# LED_segment.net
KiCad netlist of a schematic drawn in EAGLE
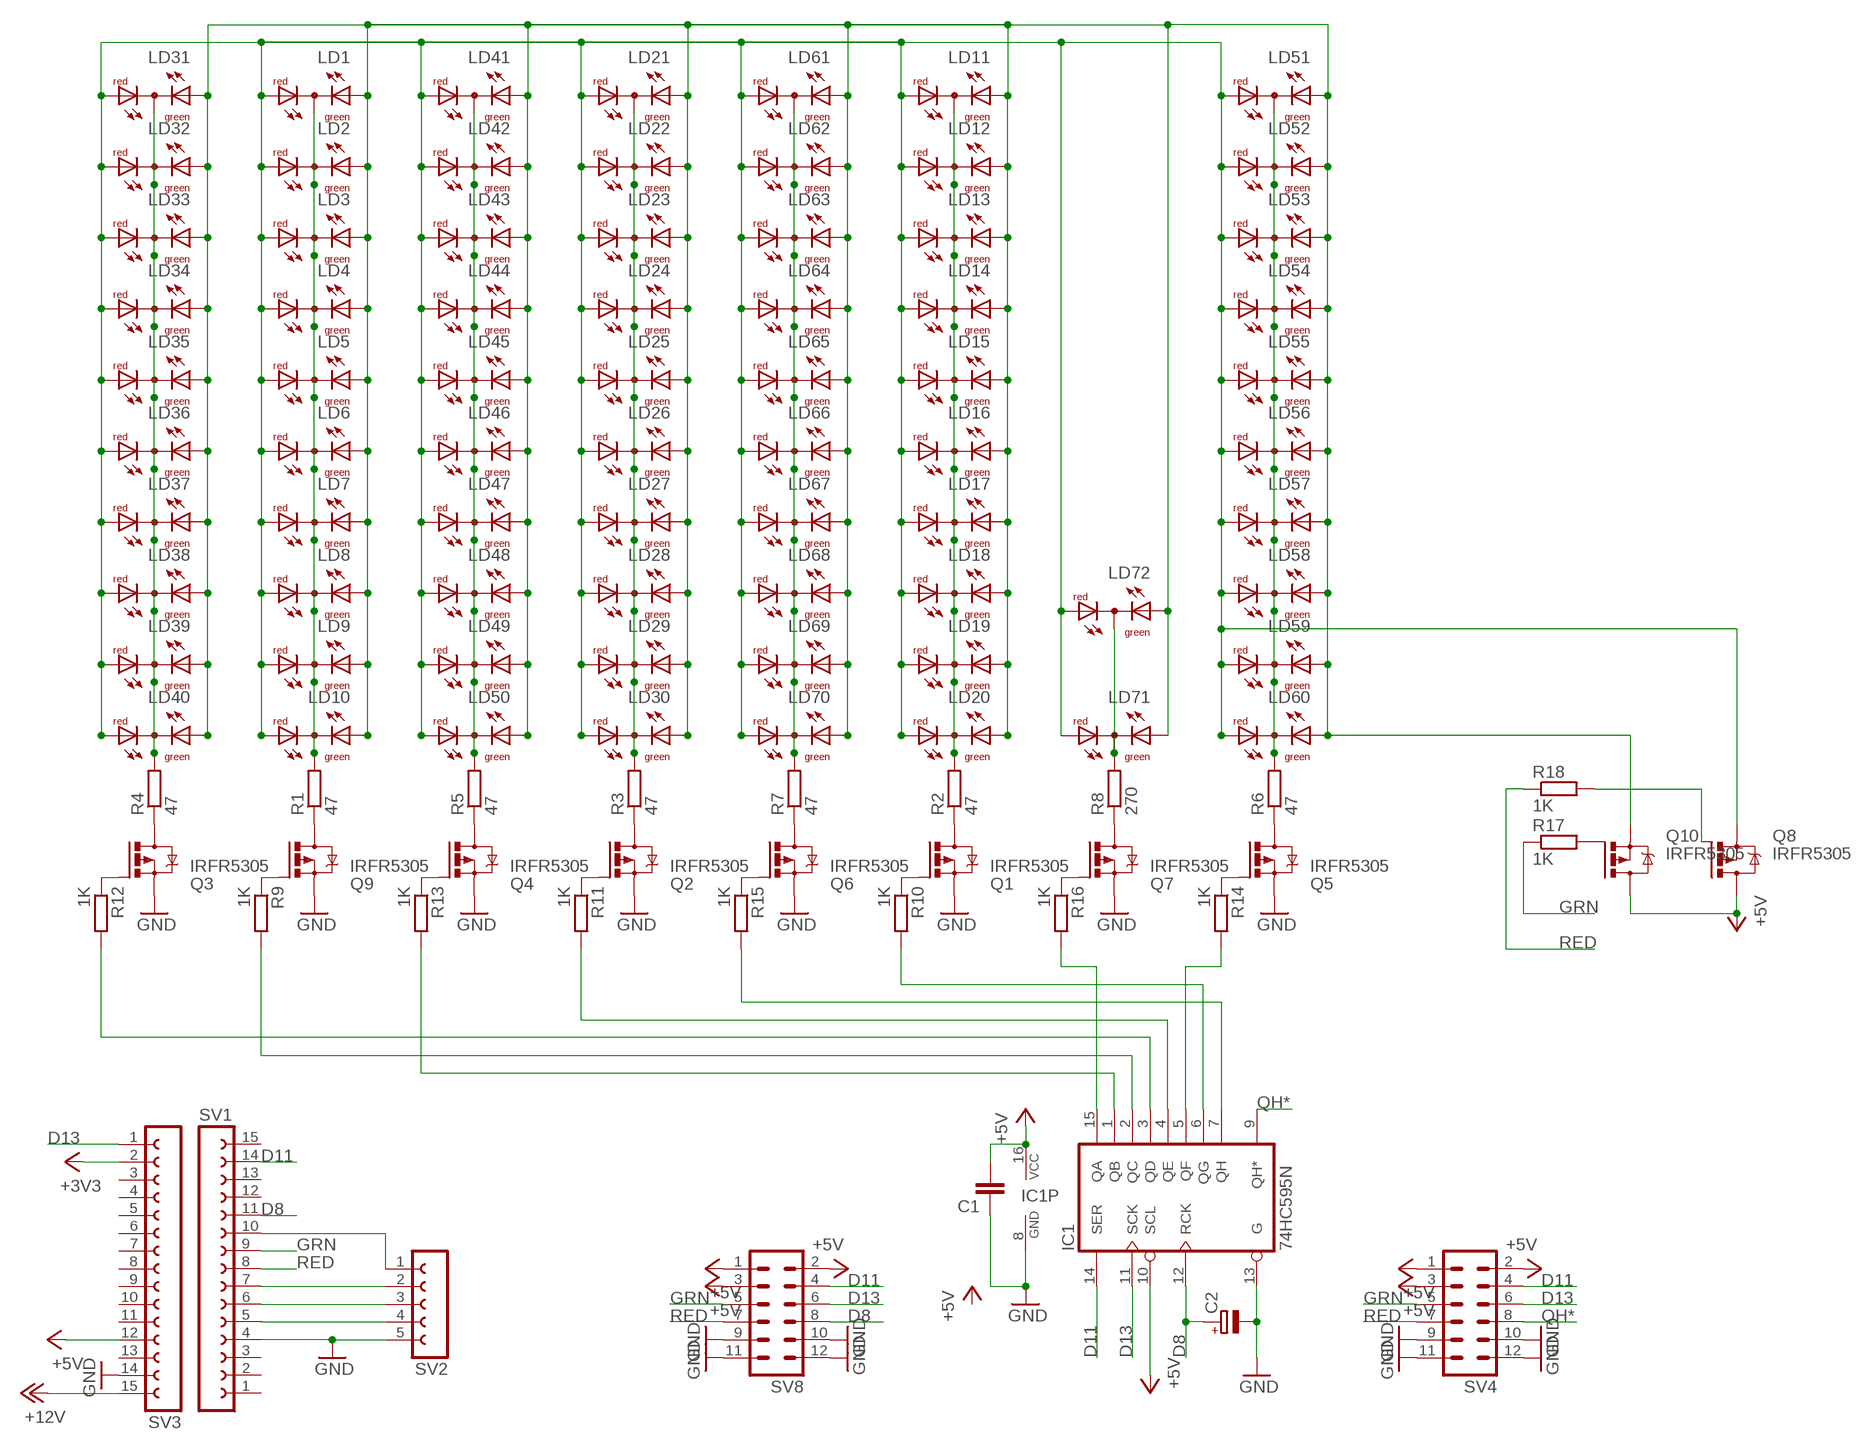
[diagram p0: schematic, sheet 1]

(export (version "E")
  (design (tool "Eeschema 10.0.6"))
  (components
    (comp (ref "C1")
      (value "C-EU050-030X075")
      (footprint "eagle-import:C050-030X075")
      (libsource (lib "eagle-import") (part "C-EU050-030X075"))
    )
    (comp (ref "C2")
      (value "CPOL-EUE2.5-7")
      (footprint "eagle-import:E2,5-7")
      (libsource (lib "eagle-import") (part "CPOL-EUE2.5-7"))
    )
    (comp (ref "IC1")
      (value "74HC595N")
      (footprint "eagle-import:DIL16")
      (libsource (lib "eagle-import") (part "74595NHC"))
    )
    (comp (ref "LD1")
      (value "DUOLED-RG-C")
      (footprint "eagle-import:DUOLED-C-5MM")
      (libsource (lib "eagle-import") (part "DUOLED-RG-C"))
    )
    (comp (ref "LD2")
      (value "DUOLED-RG-C")
      (footprint "eagle-import:DUOLED-C-5MM")
      (libsource (lib "eagle-import") (part "DUOLED-RG-C"))
    )
    (comp (ref "LD3")
      (value "DUOLED-RG-C")
      (footprint "eagle-import:DUOLED-C-5MM")
      (libsource (lib "eagle-import") (part "DUOLED-RG-C"))
    )
    (comp (ref "LD4")
      (value "DUOLED-RG-C")
      (footprint "eagle-import:DUOLED-C-5MM")
      (libsource (lib "eagle-import") (part "DUOLED-RG-C"))
    )
    (comp (ref "LD5")
      (value "DUOLED-RG-C")
      (footprint "eagle-import:DUOLED-C-5MM")
      (libsource (lib "eagle-import") (part "DUOLED-RG-C"))
    )
    (comp (ref "LD6")
      (value "DUOLED-RG-C")
      (footprint "eagle-import:DUOLED-C-5MM")
      (libsource (lib "eagle-import") (part "DUOLED-RG-C"))
    )
    (comp (ref "LD7")
      (value "DUOLED-RG-C")
      (footprint "eagle-import:DUOLED-C-5MM")
      (libsource (lib "eagle-import") (part "DUOLED-RG-C"))
    )
    (comp (ref "LD8")
      (value "DUOLED-RG-C")
      (footprint "eagle-import:DUOLED-C-5MM")
      (libsource (lib "eagle-import") (part "DUOLED-RG-C"))
    )
    (comp (ref "LD9")
      (value "DUOLED-RG-C")
      (footprint "eagle-import:DUOLED-C-5MM")
      (libsource (lib "eagle-import") (part "DUOLED-RG-C"))
    )
    (comp (ref "LD10")
      (value "DUOLED-RG-C")
      (footprint "eagle-import:DUOLED-C-5MM")
      (libsource (lib "eagle-import") (part "DUOLED-RG-C"))
    )
    (comp (ref "LD11")
      (value "DUOLED-RG-C")
      (footprint "eagle-import:DUOLED-C-5MM")
      (libsource (lib "eagle-import") (part "DUOLED-RG-C"))
    )
    (comp (ref "LD12")
      (value "DUOLED-RG-C")
      (footprint "eagle-import:DUOLED-C-5MM")
      (libsource (lib "eagle-import") (part "DUOLED-RG-C"))
    )
    (comp (ref "LD13")
      (value "DUOLED-RG-C")
      (footprint "eagle-import:DUOLED-C-5MM")
      (libsource (lib "eagle-import") (part "DUOLED-RG-C"))
    )
    (comp (ref "LD14")
      (value "DUOLED-RG-C")
      (footprint "eagle-import:DUOLED-C-5MM")
      (libsource (lib "eagle-import") (part "DUOLED-RG-C"))
    )
    (comp (ref "LD15")
      (value "DUOLED-RG-C")
      (footprint "eagle-import:DUOLED-C-5MM")
      (libsource (lib "eagle-import") (part "DUOLED-RG-C"))
    )
    (comp (ref "LD16")
      (value "DUOLED-RG-C")
      (footprint "eagle-import:DUOLED-C-5MM")
      (libsource (lib "eagle-import") (part "DUOLED-RG-C"))
    )
    (comp (ref "LD17")
      (value "DUOLED-RG-C")
      (footprint "eagle-import:DUOLED-C-5MM")
      (libsource (lib "eagle-import") (part "DUOLED-RG-C"))
    )
    (comp (ref "LD18")
      (value "DUOLED-RG-C")
      (footprint "eagle-import:DUOLED-C-5MM")
      (libsource (lib "eagle-import") (part "DUOLED-RG-C"))
    )
    (comp (ref "LD19")
      (value "DUOLED-RG-C")
      (footprint "eagle-import:DUOLED-C-5MM")
      (libsource (lib "eagle-import") (part "DUOLED-RG-C"))
    )
    (comp (ref "LD20")
      (value "DUOLED-RG-C")
      (footprint "eagle-import:DUOLED-C-5MM")
      (libsource (lib "eagle-import") (part "DUOLED-RG-C"))
    )
    (comp (ref "LD21")
      (value "DUOLED-RG-C")
      (footprint "eagle-import:DUOLED-C-5MM")
      (libsource (lib "eagle-import") (part "DUOLED-RG-C"))
    )
    (comp (ref "LD22")
      (value "DUOLED-RG-C")
      (footprint "eagle-import:DUOLED-C-5MM")
      (libsource (lib "eagle-import") (part "DUOLED-RG-C"))
    )
    (comp (ref "LD23")
      (value "DUOLED-RG-C")
      (footprint "eagle-import:DUOLED-C-5MM")
      (libsource (lib "eagle-import") (part "DUOLED-RG-C"))
    )
    (comp (ref "LD24")
      (value "DUOLED-RG-C")
      (footprint "eagle-import:DUOLED-C-5MM")
      (libsource (lib "eagle-import") (part "DUOLED-RG-C"))
    )
    (comp (ref "LD25")
      (value "DUOLED-RG-C")
      (footprint "eagle-import:DUOLED-C-5MM")
      (libsource (lib "eagle-import") (part "DUOLED-RG-C"))
    )
    (comp (ref "LD26")
      (value "DUOLED-RG-C")
      (footprint "eagle-import:DUOLED-C-5MM")
      (libsource (lib "eagle-import") (part "DUOLED-RG-C"))
    )
    (comp (ref "LD27")
      (value "DUOLED-RG-C")
      (footprint "eagle-import:DUOLED-C-5MM")
      (libsource (lib "eagle-import") (part "DUOLED-RG-C"))
    )
    (comp (ref "LD28")
      (value "DUOLED-RG-C")
      (footprint "eagle-import:DUOLED-C-5MM")
      (libsource (lib "eagle-import") (part "DUOLED-RG-C"))
    )
    (comp (ref "LD29")
      (value "DUOLED-RG-C")
      (footprint "eagle-import:DUOLED-C-5MM")
      (libsource (lib "eagle-import") (part "DUOLED-RG-C"))
    )
    (comp (ref "LD30")
      (value "DUOLED-RG-C")
      (footprint "eagle-import:DUOLED-C-5MM")
      (libsource (lib "eagle-import") (part "DUOLED-RG-C"))
    )
    (comp (ref "LD31")
      (value "DUOLED-RG-C")
      (footprint "eagle-import:DUOLED-C-5MM")
      (libsource (lib "eagle-import") (part "DUOLED-RG-C"))
    )
    (comp (ref "LD32")
      (value "DUOLED-RG-C")
      (footprint "eagle-import:DUOLED-C-5MM")
      (libsource (lib "eagle-import") (part "DUOLED-RG-C"))
    )
    (comp (ref "LD33")
      (value "DUOLED-RG-C")
      (footprint "eagle-import:DUOLED-C-5MM")
      (libsource (lib "eagle-import") (part "DUOLED-RG-C"))
    )
    (comp (ref "LD34")
      (value "DUOLED-RG-C")
      (footprint "eagle-import:DUOLED-C-5MM")
      (libsource (lib "eagle-import") (part "DUOLED-RG-C"))
    )
    (comp (ref "LD35")
      (value "DUOLED-RG-C")
      (footprint "eagle-import:DUOLED-C-5MM")
      (libsource (lib "eagle-import") (part "DUOLED-RG-C"))
    )
    (comp (ref "LD36")
      (value "DUOLED-RG-C")
      (footprint "eagle-import:DUOLED-C-5MM")
      (libsource (lib "eagle-import") (part "DUOLED-RG-C"))
    )
    (comp (ref "LD37")
      (value "DUOLED-RG-C")
      (footprint "eagle-import:DUOLED-C-5MM")
      (libsource (lib "eagle-import") (part "DUOLED-RG-C"))
    )
    (comp (ref "LD38")
      (value "DUOLED-RG-C")
      (footprint "eagle-import:DUOLED-C-5MM")
      (libsource (lib "eagle-import") (part "DUOLED-RG-C"))
    )
    (comp (ref "LD39")
      (value "DUOLED-RG-C")
      (footprint "eagle-import:DUOLED-C-5MM")
      (libsource (lib "eagle-import") (part "DUOLED-RG-C"))
    )
    (comp (ref "LD40")
      (value "DUOLED-RG-C")
      (footprint "eagle-import:DUOLED-C-5MM")
      (libsource (lib "eagle-import") (part "DUOLED-RG-C"))
    )
    (comp (ref "LD41")
      (value "DUOLED-RG-C")
      (footprint "eagle-import:DUOLED-C-5MM")
      (libsource (lib "eagle-import") (part "DUOLED-RG-C"))
    )
    (comp (ref "LD42")
      (value "DUOLED-RG-C")
      (footprint "eagle-import:DUOLED-C-5MM")
      (libsource (lib "eagle-import") (part "DUOLED-RG-C"))
    )
    (comp (ref "LD43")
      (value "DUOLED-RG-C")
      (footprint "eagle-import:DUOLED-C-5MM")
      (libsource (lib "eagle-import") (part "DUOLED-RG-C"))
    )
    (comp (ref "LD44")
      (value "DUOLED-RG-C")
      (footprint "eagle-import:DUOLED-C-5MM")
      (libsource (lib "eagle-import") (part "DUOLED-RG-C"))
    )
    (comp (ref "LD45")
      (value "DUOLED-RG-C")
      (footprint "eagle-import:DUOLED-C-5MM")
      (libsource (lib "eagle-import") (part "DUOLED-RG-C"))
    )
    (comp (ref "LD46")
      (value "DUOLED-RG-C")
      (footprint "eagle-import:DUOLED-C-5MM")
      (libsource (lib "eagle-import") (part "DUOLED-RG-C"))
    )
    (comp (ref "LD47")
      (value "DUOLED-RG-C")
      (footprint "eagle-import:DUOLED-C-5MM")
      (libsource (lib "eagle-import") (part "DUOLED-RG-C"))
    )
    (comp (ref "LD48")
      (value "DUOLED-RG-C")
      (footprint "eagle-import:DUOLED-C-5MM")
      (libsource (lib "eagle-import") (part "DUOLED-RG-C"))
    )
    (comp (ref "LD49")
      (value "DUOLED-RG-C")
      (footprint "eagle-import:DUOLED-C-5MM")
      (libsource (lib "eagle-import") (part "DUOLED-RG-C"))
    )
    (comp (ref "LD50")
      (value "DUOLED-RG-C")
      (footprint "eagle-import:DUOLED-C-5MM")
      (libsource (lib "eagle-import") (part "DUOLED-RG-C"))
    )
    (comp (ref "LD51")
      (value "DUOLED-RG-C")
      (footprint "eagle-import:DUOLED-C-5MM")
      (libsource (lib "eagle-import") (part "DUOLED-RG-C"))
    )
    (comp (ref "LD52")
      (value "DUOLED-RG-C")
      (footprint "eagle-import:DUOLED-C-5MM")
      (libsource (lib "eagle-import") (part "DUOLED-RG-C"))
    )
    (comp (ref "LD53")
      (value "DUOLED-RG-C")
      (footprint "eagle-import:DUOLED-C-5MM")
      (libsource (lib "eagle-import") (part "DUOLED-RG-C"))
    )
    (comp (ref "LD54")
      (value "DUOLED-RG-C")
      (footprint "eagle-import:DUOLED-C-5MM")
      (libsource (lib "eagle-import") (part "DUOLED-RG-C"))
    )
    (comp (ref "LD55")
      (value "DUOLED-RG-C")
      (footprint "eagle-import:DUOLED-C-5MM")
      (libsource (lib "eagle-import") (part "DUOLED-RG-C"))
    )
    (comp (ref "LD56")
      (value "DUOLED-RG-C")
      (footprint "eagle-import:DUOLED-C-5MM")
      (libsource (lib "eagle-import") (part "DUOLED-RG-C"))
    )
    (comp (ref "LD57")
      (value "DUOLED-RG-C")
      (footprint "eagle-import:DUOLED-C-5MM")
      (libsource (lib "eagle-import") (part "DUOLED-RG-C"))
    )
    (comp (ref "LD58")
      (value "DUOLED-RG-C")
      (footprint "eagle-import:DUOLED-C-5MM")
      (libsource (lib "eagle-import") (part "DUOLED-RG-C"))
    )
    (comp (ref "LD59")
      (value "DUOLED-RG-C")
      (footprint "eagle-import:DUOLED-C-5MM")
      (libsource (lib "eagle-import") (part "DUOLED-RG-C"))
    )
    (comp (ref "LD60")
      (value "DUOLED-RG-C")
      (footprint "eagle-import:DUOLED-C-5MM")
      (libsource (lib "eagle-import") (part "DUOLED-RG-C"))
    )
    (comp (ref "LD61")
      (value "DUOLED-RG-C")
      (footprint "eagle-import:DUOLED-C-5MM")
      (libsource (lib "eagle-import") (part "DUOLED-RG-C"))
    )
    (comp (ref "LD62")
      (value "DUOLED-RG-C")
      (footprint "eagle-import:DUOLED-C-5MM")
      (libsource (lib "eagle-import") (part "DUOLED-RG-C"))
    )
    (comp (ref "LD63")
      (value "DUOLED-RG-C")
      (footprint "eagle-import:DUOLED-C-5MM")
      (libsource (lib "eagle-import") (part "DUOLED-RG-C"))
    )
    (comp (ref "LD64")
      (value "DUOLED-RG-C")
      (footprint "eagle-import:DUOLED-C-5MM")
      (libsource (lib "eagle-import") (part "DUOLED-RG-C"))
    )
    (comp (ref "LD65")
      (value "DUOLED-RG-C")
      (footprint "eagle-import:DUOLED-C-5MM")
      (libsource (lib "eagle-import") (part "DUOLED-RG-C"))
    )
    (comp (ref "LD66")
      (value "DUOLED-RG-C")
      (footprint "eagle-import:DUOLED-C-5MM")
      (libsource (lib "eagle-import") (part "DUOLED-RG-C"))
    )
    (comp (ref "LD67")
      (value "DUOLED-RG-C")
      (footprint "eagle-import:DUOLED-C-5MM")
      (libsource (lib "eagle-import") (part "DUOLED-RG-C"))
    )
    (comp (ref "LD68")
      (value "DUOLED-RG-C")
      (footprint "eagle-import:DUOLED-C-5MM")
      (libsource (lib "eagle-import") (part "DUOLED-RG-C"))
    )
    (comp (ref "LD69")
      (value "DUOLED-RG-C")
      (footprint "eagle-import:DUOLED-C-5MM")
      (libsource (lib "eagle-import") (part "DUOLED-RG-C"))
    )
    (comp (ref "LD70")
      (value "DUOLED-RG-C")
      (footprint "eagle-import:DUOLED-C-5MM")
      (libsource (lib "eagle-import") (part "DUOLED-RG-C"))
    )
    (comp (ref "LD71")
      (value "DUOLED-RG-C")
      (footprint "eagle-import:DUOLED-C-5MM")
      (libsource (lib "eagle-import") (part "DUOLED-RG-C"))
    )
    (comp (ref "LD72")
      (value "DUOLED-RG-C")
      (footprint "eagle-import:DUOLED-C-5MM")
      (libsource (lib "eagle-import") (part "DUOLED-RG-C"))
    )
    (comp (ref "Q1")
      (value "IRFR5305")
      (footprint "eagle-import:D-PAK_TO252AA")
      (libsource (lib "eagle-import") (part "IRF?5305R"))
    )
    (comp (ref "Q2")
      (value "IRFR5305")
      (footprint "eagle-import:D-PAK_TO252AA")
      (libsource (lib "eagle-import") (part "IRF?5305R"))
    )
    (comp (ref "Q3")
      (value "IRFR5305")
      (footprint "eagle-import:D-PAK_TO252AA")
      (libsource (lib "eagle-import") (part "IRF?5305R"))
    )
    (comp (ref "Q4")
      (value "IRFR5305")
      (footprint "eagle-import:D-PAK_TO252AA")
      (libsource (lib "eagle-import") (part "IRF?5305R"))
    )
    (comp (ref "Q5")
      (value "IRFR5305")
      (footprint "eagle-import:D-PAK_TO252AA")
      (libsource (lib "eagle-import") (part "IRF?5305R"))
    )
    (comp (ref "Q6")
      (value "IRFR5305")
      (footprint "eagle-import:D-PAK_TO252AA")
      (libsource (lib "eagle-import") (part "IRF?5305R"))
    )
    (comp (ref "Q7")
      (value "IRFR5305")
      (footprint "eagle-import:D-PAK_TO252AA")
      (libsource (lib "eagle-import") (part "IRF?5305R"))
    )
    (comp (ref "Q8")
      (value "IRFR5305")
      (footprint "eagle-import:D-PAK_TO252AA")
      (libsource (lib "eagle-import") (part "IRF?5305R"))
    )
    (comp (ref "Q9")
      (value "IRFR5305")
      (footprint "eagle-import:D-PAK_TO252AA")
      (libsource (lib "eagle-import") (part "IRF?5305R"))
    )
    (comp (ref "Q10")
      (value "IRFR5305")
      (footprint "eagle-import:D-PAK_TO252AA")
      (libsource (lib "eagle-import") (part "IRF?5305R"))
    )
    (comp (ref "R1")
      (value "47")
      (footprint "eagle-import:0204_7")
      (libsource (lib "eagle-import") (part "R-EU_0204/7"))
    )
    (comp (ref "R2")
      (value "47")
      (footprint "eagle-import:0204_7")
      (libsource (lib "eagle-import") (part "R-EU_0204/7"))
    )
    (comp (ref "R3")
      (value "47")
      (footprint "eagle-import:0204_7")
      (libsource (lib "eagle-import") (part "R-EU_0204/7"))
    )
    (comp (ref "R4")
      (value "47")
      (footprint "eagle-import:0204_7")
      (libsource (lib "eagle-import") (part "R-EU_0204/7"))
    )
    (comp (ref "R5")
      (value "47")
      (footprint "eagle-import:0204_7")
      (libsource (lib "eagle-import") (part "R-EU_0204/7"))
    )
    (comp (ref "R6")
      (value "47")
      (footprint "eagle-import:0204_7")
      (libsource (lib "eagle-import") (part "R-EU_0204/7"))
    )
    (comp (ref "R7")
      (value "47")
      (footprint "eagle-import:0207_5V")
      (libsource (lib "eagle-import") (part "R-EU_0207/5V"))
    )
    (comp (ref "R8")
      (value "270")
      (footprint "eagle-import:0204_7")
      (libsource (lib "eagle-import") (part "R-EU_0204/7"))
    )
    (comp (ref "R9")
      (value "1K")
      (footprint "eagle-import:0204_7")
      (libsource (lib "eagle-import") (part "R-EU_0204/7"))
    )
    (comp (ref "R10")
      (value "1K")
      (footprint "eagle-import:0204_7")
      (libsource (lib "eagle-import") (part "R-EU_0204/7"))
    )
    (comp (ref "R11")
      (value "1K")
      (footprint "eagle-import:0204_7")
      (libsource (lib "eagle-import") (part "R-EU_0204/7"))
    )
    (comp (ref "R12")
      (value "1K")
      (footprint "eagle-import:0204_7")
      (libsource (lib "eagle-import") (part "R-EU_0204/7"))
    )
    (comp (ref "R13")
      (value "1K")
      (footprint "eagle-import:0204_7")
      (libsource (lib "eagle-import") (part "R-EU_0204/7"))
    )
    (comp (ref "R14")
      (value "1K")
      (footprint "eagle-import:0204_7")
      (libsource (lib "eagle-import") (part "R-EU_0204/7"))
    )
    (comp (ref "R15")
      (value "1K")
      (footprint "eagle-import:0204_7")
      (libsource (lib "eagle-import") (part "R-EU_0204/7"))
    )
    (comp (ref "R16")
      (value "1K")
      (footprint "eagle-import:0204_7")
      (libsource (lib "eagle-import") (part "R-EU_0204/7"))
    )
    (comp (ref "R17")
      (value "1K")
      (footprint "eagle-import:0204_7")
      (libsource (lib "eagle-import") (part "R-EU_0204/7"))
    )
    (comp (ref "R18")
      (value "1K")
      (footprint "eagle-import:0204_7")
      (libsource (lib "eagle-import") (part "R-EU_0204/7"))
    )
    (comp (ref "SV1")
      (value "FE15-1")
      (footprint "eagle-import:FE15")
      (libsource (lib "eagle-import") (part "FE15-1"))
    )
    (comp (ref "SV2")
      (value "FE05-1")
      (footprint "eagle-import:FE05-1")
      (libsource (lib "eagle-import") (part "FE05-1"))
    )
    (comp (ref "SV3")
      (value "FE15-1")
      (footprint "eagle-import:FE15")
      (libsource (lib "eagle-import") (part "FE15-1"))
    )
    (comp (ref "SV4")
      (value "MA06-2")
      (footprint "eagle-import:MA06-2")
      (libsource (lib "eagle-import") (part "MA06-2"))
    )
    (comp (ref "SV8")
      (value "MA06-2")
      (footprint "eagle-import:MA06-2")
      (libsource (lib "eagle-import") (part "MA06-2"))
    )
  )
  (nets
    (net (code "1") (name "+3V3") (class "Default")
      (node (ref "SV3") (pin "2") (pinfunction "2_2") (pintype "passive"))
    )
    (net (code "2") (name "+5V") (class "Default")
      (node (ref "C1") (pin "2") (pinfunction "2_2") (pintype "passive"))
      (node (ref "IC1") (pin "10") (pinfunction "SCL_10") (pintype "input"))
      (node (ref "IC1") (pin "16") (pinfunction "VCC_16") (pintype "power_in"))
      (node (ref "Q10") (pin "4") (pinfunction "D_4") (pintype "passive"))
      (node (ref "Q8") (pin "4") (pinfunction "D_4") (pintype "passive"))
      (node (ref "SV3") (pin "12") (pinfunction "12_12") (pintype "passive"))
      (node (ref "SV4") (pin "1") (pinfunction "1_1") (pintype "passive"))
      (node (ref "SV4") (pin "2") (pinfunction "2_2") (pintype "passive"))
      (node (ref "SV4") (pin "3") (pinfunction "3_3") (pintype "passive"))
      (node (ref "SV8") (pin "1") (pinfunction "1_1") (pintype "passive"))
      (node (ref "SV8") (pin "2") (pinfunction "2_2") (pintype "passive"))
      (node (ref "SV8") (pin "3") (pinfunction "3_3") (pintype "passive"))
    )
    (net (code "3") (name "+12V") (class "Default")
      (node (ref "SV3") (pin "15") (pinfunction "15_15") (pintype "passive"))
    )
    (net (code "4") (name "/D8") (class "Default")
      (node (ref "C2") (pin "+") (pinfunction "+_+") (pintype "passive"))
      (node (ref "IC1") (pin "12") (pinfunction "RCK_12") (pintype "input"))
      (node (ref "SV1") (pin "11") (pinfunction "11_11") (pintype "passive"))
      (node (ref "SV8") (pin "8") (pinfunction "8_8") (pintype "passive"))
    )
    (net (code "5") (name "/D11") (class "Default")
      (node (ref "IC1") (pin "14") (pinfunction "SER_14") (pintype "input"))
      (node (ref "SV1") (pin "14") (pinfunction "14_14") (pintype "passive"))
      (node (ref "SV4") (pin "4") (pinfunction "4_4") (pintype "passive"))
      (node (ref "SV8") (pin "4") (pinfunction "4_4") (pintype "passive"))
    )
    (net (code "6") (name "/D13") (class "Default")
      (node (ref "IC1") (pin "11") (pinfunction "SCK_11") (pintype "input"))
      (node (ref "SV3") (pin "1") (pinfunction "1_1") (pintype "passive"))
      (node (ref "SV4") (pin "6") (pinfunction "6_6") (pintype "passive"))
      (node (ref "SV8") (pin "6") (pinfunction "6_6") (pintype "passive"))
    )
    (net (code "7") (name "/GRN") (class "Default")
      (node (ref "R17") (pin "1") (pinfunction "1_1") (pintype "passive"))
      (node (ref "SV1") (pin "9") (pinfunction "9_9") (pintype "passive"))
      (node (ref "SV4") (pin "5") (pinfunction "5_5") (pintype "passive"))
      (node (ref "SV8") (pin "5") (pinfunction "5_5") (pintype "passive"))
    )
    (net (code "8") (name "/QH*") (class "Default")
      (node (ref "IC1") (pin "9") (pinfunction "QH*_9") (pintype "tri_state"))
      (node (ref "SV4") (pin "8") (pinfunction "8_8") (pintype "passive"))
    )
    (net (code "9") (name "/RED") (class "Default")
      (node (ref "R18") (pin "1") (pinfunction "1_1") (pintype "passive"))
      (node (ref "SV1") (pin "8") (pinfunction "8_8") (pintype "passive"))
      (node (ref "SV4") (pin "7") (pinfunction "7_7") (pintype "passive"))
      (node (ref "SV8") (pin "7") (pinfunction "7_7") (pintype "passive"))
    )
    (net (code "10") (name "GND") (class "Default")
      (node (ref "C1") (pin "1") (pinfunction "1_1") (pintype "passive"))
      (node (ref "C2") (pin "-") (pinfunction "-_-") (pintype "passive"))
      (node (ref "IC1") (pin "13") (pinfunction "G_13") (pintype "input"))
      (node (ref "IC1") (pin "8") (pinfunction "GND_8") (pintype "power_in"))
      (node (ref "Q1") (pin "3") (pinfunction "S_3") (pintype "passive"))
      (node (ref "Q2") (pin "3") (pinfunction "S_3") (pintype "passive"))
      (node (ref "Q3") (pin "3") (pinfunction "S_3") (pintype "passive"))
      (node (ref "Q4") (pin "3") (pinfunction "S_3") (pintype "passive"))
      (node (ref "Q5") (pin "3") (pinfunction "S_3") (pintype "passive"))
      (node (ref "Q6") (pin "3") (pinfunction "S_3") (pintype "passive"))
      (node (ref "Q7") (pin "3") (pinfunction "S_3") (pintype "passive"))
      (node (ref "Q9") (pin "3") (pinfunction "S_3") (pintype "passive"))
      (node (ref "SV1") (pin "4") (pinfunction "4_4") (pintype "passive"))
      (node (ref "SV2") (pin "5") (pinfunction "5_5") (pintype "passive"))
      (node (ref "SV3") (pin "14") (pinfunction "14_14") (pintype "passive"))
      (node (ref "SV4") (pin "10") (pinfunction "10_10") (pintype "passive"))
      (node (ref "SV4") (pin "11") (pinfunction "11_11") (pintype "passive"))
      (node (ref "SV4") (pin "12") (pinfunction "12_12") (pintype "passive"))
      (node (ref "SV4") (pin "9") (pinfunction "9_9") (pintype "passive"))
      (node (ref "SV8") (pin "10") (pinfunction "10_10") (pintype "passive"))
      (node (ref "SV8") (pin "11") (pinfunction "11_11") (pintype "passive"))
      (node (ref "SV8") (pin "12") (pinfunction "12_12") (pintype "passive"))
      (node (ref "SV8") (pin "9") (pinfunction "9_9") (pintype "passive"))
    )
    (net (code "11") (name "Net-(IC1A-QA)") (class "Default")
      (node (ref "IC1") (pin "15") (pinfunction "QA_15") (pintype "tri_state"))
      (node (ref "R16") (pin "2") (pinfunction "2_2") (pintype "passive"))
    )
    (net (code "12") (name "Net-(IC1A-QB)") (class "Default")
      (node (ref "IC1") (pin "1") (pinfunction "QB_1") (pintype "tri_state"))
      (node (ref "R13") (pin "2") (pinfunction "2_2") (pintype "passive"))
    )
    (net (code "13") (name "Net-(IC1A-QC)") (class "Default")
      (node (ref "IC1") (pin "2") (pinfunction "QC_2") (pintype "tri_state"))
      (node (ref "R9") (pin "2") (pinfunction "2_2") (pintype "passive"))
    )
    (net (code "14") (name "Net-(IC1A-QD)") (class "Default")
      (node (ref "IC1") (pin "3") (pinfunction "QD_3") (pintype "tri_state"))
      (node (ref "R12") (pin "2") (pinfunction "2_2") (pintype "passive"))
    )
    (net (code "15") (name "Net-(IC1A-QE)") (class "Default")
      (node (ref "IC1") (pin "4") (pinfunction "QE_4") (pintype "tri_state"))
      (node (ref "R11") (pin "2") (pinfunction "2_2") (pintype "passive"))
    )
    (net (code "16") (name "Net-(IC1A-QF)") (class "Default")
      (node (ref "IC1") (pin "5") (pinfunction "QF_5") (pintype "tri_state"))
      (node (ref "R14") (pin "2") (pinfunction "2_2") (pintype "passive"))
    )
    (net (code "17") (name "Net-(IC1A-QG)") (class "Default")
      (node (ref "IC1") (pin "6") (pinfunction "QG_6") (pintype "tri_state"))
      (node (ref "R10") (pin "2") (pinfunction "2_2") (pintype "passive"))
    )
    (net (code "18") (name "Net-(IC1A-QH)") (class "Default")
      (node (ref "IC1") (pin "7") (pinfunction "QH_7") (pintype "tri_state"))
      (node (ref "R15") (pin "2") (pinfunction "2_2") (pintype "passive"))
    )
    (net (code "19") (name "Net-(LD1-AG)") (class "Default")
      (node (ref "LD1") (pin "AX") (pinfunction "AG_AX") (pintype "passive"))
      (node (ref "LD10") (pin "AX") (pinfunction "AG_AX") (pintype "passive"))
      (node (ref "LD11") (pin "AX") (pinfunction "AG_AX") (pintype "passive"))
      (node (ref "LD12") (pin "AX") (pinfunction "AG_AX") (pintype "passive"))
      (node (ref "LD13") (pin "AX") (pinfunction "AG_AX") (pintype "passive"))
      (node (ref "LD14") (pin "AX") (pinfunction "AG_AX") (pintype "passive"))
      (node (ref "LD15") (pin "AX") (pinfunction "AG_AX") (pintype "passive"))
      (node (ref "LD16") (pin "AX") (pinfunction "AG_AX") (pintype "passive"))
      (node (ref "LD17") (pin "AX") (pinfunction "AG_AX") (pintype "passive"))
      (node (ref "LD18") (pin "AX") (pinfunction "AG_AX") (pintype "passive"))
      (node (ref "LD19") (pin "AX") (pinfunction "AG_AX") (pintype "passive"))
      (node (ref "LD2") (pin "AX") (pinfunction "AG_AX") (pintype "passive"))
      (node (ref "LD20") (pin "AX") (pinfunction "AG_AX") (pintype "passive"))
      (node (ref "LD21") (pin "AX") (pinfunction "AG_AX") (pintype "passive"))
      (node (ref "LD22") (pin "AX") (pinfunction "AG_AX") (pintype "passive"))
      (node (ref "LD23") (pin "AX") (pinfunction "AG_AX") (pintype "passive"))
      (node (ref "LD24") (pin "AX") (pinfunction "AG_AX") (pintype "passive"))
      (node (ref "LD25") (pin "AX") (pinfunction "AG_AX") (pintype "passive"))
      (node (ref "LD26") (pin "AX") (pinfunction "AG_AX") (pintype "passive"))
      (node (ref "LD27") (pin "AX") (pinfunction "AG_AX") (pintype "passive"))
      (node (ref "LD28") (pin "AX") (pinfunction "AG_AX") (pintype "passive"))
      (node (ref "LD29") (pin "AX") (pinfunction "AG_AX") (pintype "passive"))
      (node (ref "LD3") (pin "AX") (pinfunction "AG_AX") (pintype "passive"))
      (node (ref "LD30") (pin "AX") (pinfunction "AG_AX") (pintype "passive"))
      (node (ref "LD31") (pin "AX") (pinfunction "AG_AX") (pintype "passive"))
      (node (ref "LD32") (pin "AX") (pinfunction "AG_AX") (pintype "passive"))
      (node (ref "LD33") (pin "AX") (pinfunction "AG_AX") (pintype "passive"))
      (node (ref "LD34") (pin "AX") (pinfunction "AG_AX") (pintype "passive"))
      (node (ref "LD35") (pin "AX") (pinfunction "AG_AX") (pintype "passive"))
      (node (ref "LD36") (pin "AX") (pinfunction "AG_AX") (pintype "passive"))
      (node (ref "LD37") (pin "AX") (pinfunction "AG_AX") (pintype "passive"))
      (node (ref "LD38") (pin "AX") (pinfunction "AG_AX") (pintype "passive"))
      (node (ref "LD39") (pin "AX") (pinfunction "AG_AX") (pintype "passive"))
      (node (ref "LD4") (pin "AX") (pinfunction "AG_AX") (pintype "passive"))
      (node (ref "LD40") (pin "AX") (pinfunction "AG_AX") (pintype "passive"))
      (node (ref "LD41") (pin "AX") (pinfunction "AG_AX") (pintype "passive"))
      (node (ref "LD42") (pin "AX") (pinfunction "AG_AX") (pintype "passive"))
      (node (ref "LD43") (pin "AX") (pinfunction "AG_AX") (pintype "passive"))
      (node (ref "LD44") (pin "AX") (pinfunction "AG_AX") (pintype "passive"))
      (node (ref "LD45") (pin "AX") (pinfunction "AG_AX") (pintype "passive"))
      (node (ref "LD46") (pin "AX") (pinfunction "AG_AX") (pintype "passive"))
      (node (ref "LD47") (pin "AX") (pinfunction "AG_AX") (pintype "passive"))
      (node (ref "LD48") (pin "AX") (pinfunction "AG_AX") (pintype "passive"))
      (node (ref "LD49") (pin "AX") (pinfunction "AG_AX") (pintype "passive"))
      (node (ref "LD5") (pin "AX") (pinfunction "AG_AX") (pintype "passive"))
      (node (ref "LD50") (pin "AX") (pinfunction "AG_AX") (pintype "passive"))
      (node (ref "LD51") (pin "AX") (pinfunction "AG_AX") (pintype "passive"))
      (node (ref "LD52") (pin "AX") (pinfunction "AG_AX") (pintype "passive"))
      (node (ref "LD53") (pin "AX") (pinfunction "AG_AX") (pintype "passive"))
      (node (ref "LD54") (pin "AX") (pinfunction "AG_AX") (pintype "passive"))
      (node (ref "LD55") (pin "AX") (pinfunction "AG_AX") (pintype "passive"))
      (node (ref "LD56") (pin "AX") (pinfunction "AG_AX") (pintype "passive"))
      (node (ref "LD57") (pin "AX") (pinfunction "AG_AX") (pintype "passive"))
      (node (ref "LD58") (pin "AX") (pinfunction "AG_AX") (pintype "passive"))
      (node (ref "LD59") (pin "AX") (pinfunction "AG_AX") (pintype "passive"))
      (node (ref "LD6") (pin "AX") (pinfunction "AG_AX") (pintype "passive"))
      (node (ref "LD60") (pin "AX") (pinfunction "AG_AX") (pintype "passive"))
      (node (ref "LD61") (pin "AX") (pinfunction "AG_AX") (pintype "passive"))
      (node (ref "LD62") (pin "AX") (pinfunction "AG_AX") (pintype "passive"))
      (node (ref "LD63") (pin "AX") (pinfunction "AG_AX") (pintype "passive"))
      (node (ref "LD64") (pin "AX") (pinfunction "AG_AX") (pintype "passive"))
      (node (ref "LD65") (pin "AX") (pinfunction "AG_AX") (pintype "passive"))
      (node (ref "LD66") (pin "AX") (pinfunction "AG_AX") (pintype "passive"))
      (node (ref "LD67") (pin "AX") (pinfunction "AG_AX") (pintype "passive"))
      (node (ref "LD68") (pin "AX") (pinfunction "AG_AX") (pintype "passive"))
      (node (ref "LD69") (pin "AX") (pinfunction "AG_AX") (pintype "passive"))
      (node (ref "LD7") (pin "AX") (pinfunction "AG_AX") (pintype "passive"))
      (node (ref "LD70") (pin "AX") (pinfunction "AG_AX") (pintype "passive"))
      (node (ref "LD71") (pin "AX") (pinfunction "AG_AX") (pintype "passive"))
      (node (ref "LD72") (pin "AX") (pinfunction "AG_AX") (pintype "passive"))
      (node (ref "LD8") (pin "AX") (pinfunction "AG_AX") (pintype "passive"))
      (node (ref "LD9") (pin "AX") (pinfunction "AG_AX") (pintype "passive"))
      (node (ref "Q10") (pin "3") (pinfunction "S_3") (pintype "passive"))
    )
    (net (code "20") (name "Net-(LD1-PadC)") (class "Default")
      (node (ref "LD1") (pin "C") (pinfunction "C_C") (pintype "passive"))
      (node (ref "LD10") (pin "C") (pinfunction "C_C") (pintype "passive"))
      (node (ref "LD2") (pin "C") (pinfunction "C_C") (pintype "passive"))
      (node (ref "LD3") (pin "C") (pinfunction "C_C") (pintype "passive"))
      (node (ref "LD4") (pin "C") (pinfunction "C_C") (pintype "passive"))
      (node (ref "LD5") (pin "C") (pinfunction "C_C") (pintype "passive"))
      (node (ref "LD6") (pin "C") (pinfunction "C_C") (pintype "passive"))
      (node (ref "LD7") (pin "C") (pinfunction "C_C") (pintype "passive"))
      (node (ref "LD8") (pin "C") (pinfunction "C_C") (pintype "passive"))
      (node (ref "LD9") (pin "C") (pinfunction "C_C") (pintype "passive"))
      (node (ref "R1") (pin "2") (pinfunction "2_2") (pintype "passive"))
    )
    (net (code "21") (name "Net-(LD11-PadC)") (class "Default")
      (node (ref "LD11") (pin "C") (pinfunction "C_C") (pintype "passive"))
      (node (ref "LD12") (pin "C") (pinfunction "C_C") (pintype "passive"))
      (node (ref "LD13") (pin "C") (pinfunction "C_C") (pintype "passive"))
      (node (ref "LD14") (pin "C") (pinfunction "C_C") (pintype "passive"))
      (node (ref "LD15") (pin "C") (pinfunction "C_C") (pintype "passive"))
      (node (ref "LD16") (pin "C") (pinfunction "C_C") (pintype "passive"))
      (node (ref "LD17") (pin "C") (pinfunction "C_C") (pintype "passive"))
      (node (ref "LD18") (pin "C") (pinfunction "C_C") (pintype "passive"))
      (node (ref "LD19") (pin "C") (pinfunction "C_C") (pintype "passive"))
      (node (ref "LD20") (pin "C") (pinfunction "C_C") (pintype "passive"))
      (node (ref "R2") (pin "2") (pinfunction "2_2") (pintype "passive"))
    )
    (net (code "22") (name "Net-(LD21-PadC)") (class "Default")
      (node (ref "LD21") (pin "C") (pinfunction "C_C") (pintype "passive"))
      (node (ref "LD22") (pin "C") (pinfunction "C_C") (pintype "passive"))
      (node (ref "LD23") (pin "C") (pinfunction "C_C") (pintype "passive"))
      (node (ref "LD24") (pin "C") (pinfunction "C_C") (pintype "passive"))
      (node (ref "LD25") (pin "C") (pinfunction "C_C") (pintype "passive"))
      (node (ref "LD26") (pin "C") (pinfunction "C_C") (pintype "passive"))
      (node (ref "LD27") (pin "C") (pinfunction "C_C") (pintype "passive"))
      (node (ref "LD28") (pin "C") (pinfunction "C_C") (pintype "passive"))
      (node (ref "LD29") (pin "C") (pinfunction "C_C") (pintype "passive"))
      (node (ref "LD30") (pin "C") (pinfunction "C_C") (pintype "passive"))
      (node (ref "R3") (pin "2") (pinfunction "2_2") (pintype "passive"))
    )
    (net (code "23") (name "Net-(LD31-PadC)") (class "Default")
      (node (ref "LD31") (pin "C") (pinfunction "C_C") (pintype "passive"))
      (node (ref "LD32") (pin "C") (pinfunction "C_C") (pintype "passive"))
      (node (ref "LD33") (pin "C") (pinfunction "C_C") (pintype "passive"))
      (node (ref "LD34") (pin "C") (pinfunction "C_C") (pintype "passive"))
      (node (ref "LD35") (pin "C") (pinfunction "C_C") (pintype "passive"))
      (node (ref "LD36") (pin "C") (pinfunction "C_C") (pintype "passive"))
      (node (ref "LD37") (pin "C") (pinfunction "C_C") (pintype "passive"))
      (node (ref "LD38") (pin "C") (pinfunction "C_C") (pintype "passive"))
      (node (ref "LD39") (pin "C") (pinfunction "C_C") (pintype "passive"))
      (node (ref "LD40") (pin "C") (pinfunction "C_C") (pintype "passive"))
      (node (ref "R4") (pin "2") (pinfunction "2_2") (pintype "passive"))
    )
    (net (code "24") (name "Net-(LD41-PadC)") (class "Default")
      (node (ref "LD41") (pin "C") (pinfunction "C_C") (pintype "passive"))
      (node (ref "LD42") (pin "C") (pinfunction "C_C") (pintype "passive"))
      (node (ref "LD43") (pin "C") (pinfunction "C_C") (pintype "passive"))
      (node (ref "LD44") (pin "C") (pinfunction "C_C") (pintype "passive"))
      (node (ref "LD45") (pin "C") (pinfunction "C_C") (pintype "passive"))
      (node (ref "LD46") (pin "C") (pinfunction "C_C") (pintype "passive"))
      (node (ref "LD47") (pin "C") (pinfunction "C_C") (pintype "passive"))
      (node (ref "LD48") (pin "C") (pinfunction "C_C") (pintype "passive"))
      (node (ref "LD49") (pin "C") (pinfunction "C_C") (pintype "passive"))
      (node (ref "LD50") (pin "C") (pinfunction "C_C") (pintype "passive"))
      (node (ref "R5") (pin "2") (pinfunction "2_2") (pintype "passive"))
    )
    (net (code "25") (name "Net-(LD51-PadC)") (class "Default")
      (node (ref "LD51") (pin "C") (pinfunction "C_C") (pintype "passive"))
      (node (ref "LD52") (pin "C") (pinfunction "C_C") (pintype "passive"))
      (node (ref "LD53") (pin "C") (pinfunction "C_C") (pintype "passive"))
      (node (ref "LD54") (pin "C") (pinfunction "C_C") (pintype "passive"))
      (node (ref "LD55") (pin "C") (pinfunction "C_C") (pintype "passive"))
      (node (ref "LD56") (pin "C") (pinfunction "C_C") (pintype "passive"))
      (node (ref "LD57") (pin "C") (pinfunction "C_C") (pintype "passive"))
      (node (ref "LD58") (pin "C") (pinfunction "C_C") (pintype "passive"))
      (node (ref "LD59") (pin "C") (pinfunction "C_C") (pintype "passive"))
      (node (ref "LD60") (pin "C") (pinfunction "C_C") (pintype "passive"))
      (node (ref "R6") (pin "2") (pinfunction "2_2") (pintype "passive"))
    )
    (net (code "26") (name "Net-(LD61-PadC)") (class "Default")
      (node (ref "LD61") (pin "C") (pinfunction "C_C") (pintype "passive"))
      (node (ref "LD62") (pin "C") (pinfunction "C_C") (pintype "passive"))
      (node (ref "LD63") (pin "C") (pinfunction "C_C") (pintype "passive"))
      (node (ref "LD64") (pin "C") (pinfunction "C_C") (pintype "passive"))
      (node (ref "LD65") (pin "C") (pinfunction "C_C") (pintype "passive"))
      (node (ref "LD66") (pin "C") (pinfunction "C_C") (pintype "passive"))
      (node (ref "LD67") (pin "C") (pinfunction "C_C") (pintype "passive"))
      (node (ref "LD68") (pin "C") (pinfunction "C_C") (pintype "passive"))
      (node (ref "LD69") (pin "C") (pinfunction "C_C") (pintype "passive"))
      (node (ref "LD70") (pin "C") (pinfunction "C_C") (pintype "passive"))
      (node (ref "R7") (pin "2") (pinfunction "2_2") (pintype "passive"))
    )
    (net (code "27") (name "Net-(LD71-PadC)") (class "Default")
      (node (ref "LD71") (pin "C") (pinfunction "C_C") (pintype "passive"))
      (node (ref "LD72") (pin "C") (pinfunction "C_C") (pintype "passive"))
      (node (ref "R8") (pin "2") (pinfunction "2_2") (pintype "passive"))
    )
    (net (code "28") (name "Net-(Q1-D)") (class "Default")
      (node (ref "Q1") (pin "4") (pinfunction "D_4") (pintype "passive"))
      (node (ref "R2") (pin "1") (pinfunction "1_1") (pintype "passive"))
    )
    (net (code "29") (name "Net-(Q1-G)") (class "Default")
      (node (ref "Q1") (pin "1") (pinfunction "G_1") (pintype "passive"))
      (node (ref "R10") (pin "1") (pinfunction "1_1") (pintype "passive"))
    )
    (net (code "30") (name "Net-(Q2-D)") (class "Default")
      (node (ref "Q2") (pin "4") (pinfunction "D_4") (pintype "passive"))
      (node (ref "R3") (pin "1") (pinfunction "1_1") (pintype "passive"))
    )
    (net (code "31") (name "Net-(Q2-G)") (class "Default")
      (node (ref "Q2") (pin "1") (pinfunction "G_1") (pintype "passive"))
      (node (ref "R11") (pin "1") (pinfunction "1_1") (pintype "passive"))
    )
    (net (code "32") (name "Net-(Q3-D)") (class "Default")
      (node (ref "Q3") (pin "4") (pinfunction "D_4") (pintype "passive"))
      (node (ref "R4") (pin "1") (pinfunction "1_1") (pintype "passive"))
    )
    (net (code "33") (name "Net-(Q3-G)") (class "Default")
      (node (ref "Q3") (pin "1") (pinfunction "G_1") (pintype "passive"))
      (node (ref "R12") (pin "1") (pinfunction "1_1") (pintype "passive"))
    )
    (net (code "34") (name "Net-(Q4-D)") (class "Default")
      (node (ref "Q4") (pin "4") (pinfunction "D_4") (pintype "passive"))
      (node (ref "R5") (pin "1") (pinfunction "1_1") (pintype "passive"))
    )
    (net (code "35") (name "Net-(Q4-G)") (class "Default")
      (node (ref "Q4") (pin "1") (pinfunction "G_1") (pintype "passive"))
      (node (ref "R13") (pin "1") (pinfunction "1_1") (pintype "passive"))
    )
    (net (code "36") (name "Net-(Q5-D)") (class "Default")
      (node (ref "Q5") (pin "4") (pinfunction "D_4") (pintype "passive"))
      (node (ref "R6") (pin "1") (pinfunction "1_1") (pintype "passive"))
    )
    (net (code "37") (name "Net-(Q5-G)") (class "Default")
      (node (ref "Q5") (pin "1") (pinfunction "G_1") (pintype "passive"))
      (node (ref "R14") (pin "1") (pinfunction "1_1") (pintype "passive"))
    )
    (net (code "38") (name "Net-(Q6-D)") (class "Default")
      (node (ref "Q6") (pin "4") (pinfunction "D_4") (pintype "passive"))
      (node (ref "R7") (pin "1") (pinfunction "1_1") (pintype "passive"))
    )
    (net (code "39") (name "Net-(Q6-G)") (class "Default")
      (node (ref "Q6") (pin "1") (pinfunction "G_1") (pintype "passive"))
      (node (ref "R15") (pin "1") (pinfunction "1_1") (pintype "passive"))
    )
    (net (code "40") (name "Net-(Q7-D)") (class "Default")
      (node (ref "Q7") (pin "4") (pinfunction "D_4") (pintype "passive"))
      (node (ref "R8") (pin "1") (pinfunction "1_1") (pintype "passive"))
    )
    (net (code "41") (name "Net-(Q7-G)") (class "Default")
      (node (ref "Q7") (pin "1") (pinfunction "G_1") (pintype "passive"))
      (node (ref "R16") (pin "1") (pinfunction "1_1") (pintype "passive"))
    )
    (net (code "42") (name "Net-(Q8-G)") (class "Default")
      (node (ref "Q8") (pin "1") (pinfunction "G_1") (pintype "passive"))
      (node (ref "R18") (pin "2") (pinfunction "2_2") (pintype "passive"))
    )
    (net (code "43") (name "Net-(Q8-S)") (class "Default")
      (node (ref "LD1") (pin "AR") (pinfunction "AR_AR") (pintype "passive"))
      (node (ref "LD10") (pin "AR") (pinfunction "AR_AR") (pintype "passive"))
      (node (ref "LD11") (pin "AR") (pinfunction "AR_AR") (pintype "passive"))
      (node (ref "LD12") (pin "AR") (pinfunction "AR_AR") (pintype "passive"))
      (node (ref "LD13") (pin "AR") (pinfunction "AR_AR") (pintype "passive"))
      (node (ref "LD14") (pin "AR") (pinfunction "AR_AR") (pintype "passive"))
      (node (ref "LD15") (pin "AR") (pinfunction "AR_AR") (pintype "passive"))
      (node (ref "LD16") (pin "AR") (pinfunction "AR_AR") (pintype "passive"))
      (node (ref "LD17") (pin "AR") (pinfunction "AR_AR") (pintype "passive"))
      (node (ref "LD18") (pin "AR") (pinfunction "AR_AR") (pintype "passive"))
      (node (ref "LD19") (pin "AR") (pinfunction "AR_AR") (pintype "passive"))
      (node (ref "LD2") (pin "AR") (pinfunction "AR_AR") (pintype "passive"))
      (node (ref "LD20") (pin "AR") (pinfunction "AR_AR") (pintype "passive"))
      (node (ref "LD21") (pin "AR") (pinfunction "AR_AR") (pintype "passive"))
      (node (ref "LD22") (pin "AR") (pinfunction "AR_AR") (pintype "passive"))
      (node (ref "LD23") (pin "AR") (pinfunction "AR_AR") (pintype "passive"))
      (node (ref "LD24") (pin "AR") (pinfunction "AR_AR") (pintype "passive"))
      (node (ref "LD25") (pin "AR") (pinfunction "AR_AR") (pintype "passive"))
      (node (ref "LD26") (pin "AR") (pinfunction "AR_AR") (pintype "passive"))
      (node (ref "LD27") (pin "AR") (pinfunction "AR_AR") (pintype "passive"))
      (node (ref "LD28") (pin "AR") (pinfunction "AR_AR") (pintype "passive"))
      (node (ref "LD29") (pin "AR") (pinfunction "AR_AR") (pintype "passive"))
      (node (ref "LD3") (pin "AR") (pinfunction "AR_AR") (pintype "passive"))
      (node (ref "LD30") (pin "AR") (pinfunction "AR_AR") (pintype "passive"))
      (node (ref "LD31") (pin "AR") (pinfunction "AR_AR") (pintype "passive"))
      (node (ref "LD32") (pin "AR") (pinfunction "AR_AR") (pintype "passive"))
      (node (ref "LD33") (pin "AR") (pinfunction "AR_AR") (pintype "passive"))
      (node (ref "LD34") (pin "AR") (pinfunction "AR_AR") (pintype "passive"))
      (node (ref "LD35") (pin "AR") (pinfunction "AR_AR") (pintype "passive"))
      (node (ref "LD36") (pin "AR") (pinfunction "AR_AR") (pintype "passive"))
      (node (ref "LD37") (pin "AR") (pinfunction "AR_AR") (pintype "passive"))
      (node (ref "LD38") (pin "AR") (pinfunction "AR_AR") (pintype "passive"))
      (node (ref "LD39") (pin "AR") (pinfunction "AR_AR") (pintype "passive"))
      (node (ref "LD4") (pin "AR") (pinfunction "AR_AR") (pintype "passive"))
      (node (ref "LD40") (pin "AR") (pinfunction "AR_AR") (pintype "passive"))
      (node (ref "LD41") (pin "AR") (pinfunction "AR_AR") (pintype "passive"))
      (node (ref "LD42") (pin "AR") (pinfunction "AR_AR") (pintype "passive"))
      (node (ref "LD43") (pin "AR") (pinfunction "AR_AR") (pintype "passive"))
      (node (ref "LD44") (pin "AR") (pinfunction "AR_AR") (pintype "passive"))
      (node (ref "LD45") (pin "AR") (pinfunction "AR_AR") (pintype "passive"))
      (node (ref "LD46") (pin "AR") (pinfunction "AR_AR") (pintype "passive"))
      (node (ref "LD47") (pin "AR") (pinfunction "AR_AR") (pintype "passive"))
      (node (ref "LD48") (pin "AR") (pinfunction "AR_AR") (pintype "passive"))
      (node (ref "LD49") (pin "AR") (pinfunction "AR_AR") (pintype "passive"))
      (node (ref "LD5") (pin "AR") (pinfunction "AR_AR") (pintype "passive"))
      (node (ref "LD50") (pin "AR") (pinfunction "AR_AR") (pintype "passive"))
      (node (ref "LD51") (pin "AR") (pinfunction "AR_AR") (pintype "passive"))
      (node (ref "LD52") (pin "AR") (pinfunction "AR_AR") (pintype "passive"))
      (node (ref "LD53") (pin "AR") (pinfunction "AR_AR") (pintype "passive"))
      (node (ref "LD54") (pin "AR") (pinfunction "AR_AR") (pintype "passive"))
      (node (ref "LD55") (pin "AR") (pinfunction "AR_AR") (pintype "passive"))
      (node (ref "LD56") (pin "AR") (pinfunction "AR_AR") (pintype "passive"))
      (node (ref "LD57") (pin "AR") (pinfunction "AR_AR") (pintype "passive"))
      (node (ref "LD58") (pin "AR") (pinfunction "AR_AR") (pintype "passive"))
      (node (ref "LD59") (pin "AR") (pinfunction "AR_AR") (pintype "passive"))
      (node (ref "LD6") (pin "AR") (pinfunction "AR_AR") (pintype "passive"))
      (node (ref "LD60") (pin "AR") (pinfunction "AR_AR") (pintype "passive"))
      (node (ref "LD61") (pin "AR") (pinfunction "AR_AR") (pintype "passive"))
      (node (ref "LD62") (pin "AR") (pinfunction "AR_AR") (pintype "passive"))
      (node (ref "LD63") (pin "AR") (pinfunction "AR_AR") (pintype "passive"))
      (node (ref "LD64") (pin "AR") (pinfunction "AR_AR") (pintype "passive"))
      (node (ref "LD65") (pin "AR") (pinfunction "AR_AR") (pintype "passive"))
      (node (ref "LD66") (pin "AR") (pinfunction "AR_AR") (pintype "passive"))
      (node (ref "LD67") (pin "AR") (pinfunction "AR_AR") (pintype "passive"))
      (node (ref "LD68") (pin "AR") (pinfunction "AR_AR") (pintype "passive"))
      (node (ref "LD69") (pin "AR") (pinfunction "AR_AR") (pintype "passive"))
      (node (ref "LD7") (pin "AR") (pinfunction "AR_AR") (pintype "passive"))
      (node (ref "LD70") (pin "AR") (pinfunction "AR_AR") (pintype "passive"))
      (node (ref "LD71") (pin "AR") (pinfunction "AR_AR") (pintype "passive"))
      (node (ref "LD72") (pin "AR") (pinfunction "AR_AR") (pintype "passive"))
      (node (ref "LD8") (pin "AR") (pinfunction "AR_AR") (pintype "passive"))
      (node (ref "LD9") (pin "AR") (pinfunction "AR_AR") (pintype "passive"))
      (node (ref "Q8") (pin "3") (pinfunction "S_3") (pintype "passive"))
    )
    (net (code "44") (name "Net-(Q9-D)") (class "Default")
      (node (ref "Q9") (pin "4") (pinfunction "D_4") (pintype "passive"))
      (node (ref "R1") (pin "1") (pinfunction "1_1") (pintype "passive"))
    )
    (net (code "45") (name "Net-(Q9-G)") (class "Default")
      (node (ref "Q9") (pin "1") (pinfunction "G_1") (pintype "passive"))
      (node (ref "R9") (pin "1") (pinfunction "1_1") (pintype "passive"))
    )
    (net (code "46") (name "Net-(Q10-G)") (class "Default")
      (node (ref "Q10") (pin "1") (pinfunction "G_1") (pintype "passive"))
      (node (ref "R17") (pin "2") (pinfunction "2_2") (pintype "passive"))
    )
    (net (code "47") (name "Net-(SV1-Pad5)") (class "Default")
      (node (ref "SV1") (pin "5") (pinfunction "5_5") (pintype "passive"))
      (node (ref "SV2") (pin "4") (pinfunction "4_4") (pintype "passive"))
    )
    (net (code "48") (name "Net-(SV1-Pad6)") (class "Default")
      (node (ref "SV1") (pin "6") (pinfunction "6_6") (pintype "passive"))
      (node (ref "SV2") (pin "3") (pinfunction "3_3") (pintype "passive"))
    )
    (net (code "49") (name "Net-(SV1-Pad7)") (class "Default")
      (node (ref "SV1") (pin "7") (pinfunction "7_7") (pintype "passive"))
      (node (ref "SV2") (pin "2") (pinfunction "2_2") (pintype "passive"))
    )
    (net (code "50") (name "Net-(SV1-Pad10)") (class "Default")
      (node (ref "SV1") (pin "10") (pinfunction "10_10") (pintype "passive"))
      (node (ref "SV2") (pin "1") (pinfunction "1_1") (pintype "passive"))
    )
    (net (code "51") (name "unconnected-(SV1-Pad1)") (class "Default")
      (node (ref "SV1") (pin "1") (pinfunction "1_1") (pintype "passive"))
    )
    (net (code "52") (name "unconnected-(SV1-Pad2)") (class "Default")
      (node (ref "SV1") (pin "2") (pinfunction "2_2") (pintype "passive"))
    )
    (net (code "53") (name "unconnected-(SV1-Pad3)") (class "Default")
      (node (ref "SV1") (pin "3") (pinfunction "3_3") (pintype "passive"))
    )
    (net (code "54") (name "unconnected-(SV1-Pad12)") (class "Default")
      (node (ref "SV1") (pin "12") (pinfunction "12_12") (pintype "passive"))
    )
    (net (code "55") (name "unconnected-(SV1-Pad13)") (class "Default")
      (node (ref "SV1") (pin "13") (pinfunction "13_13") (pintype "passive"))
    )
    (net (code "56") (name "unconnected-(SV1-Pad15)") (class "Default")
      (node (ref "SV1") (pin "15") (pinfunction "15_15") (pintype "passive"))
    )
    (net (code "57") (name "unconnected-(SV3-Pad3)") (class "Default")
      (node (ref "SV3") (pin "3") (pinfunction "3_3") (pintype "passive"))
    )
    (net (code "58") (name "unconnected-(SV3-Pad4)") (class "Default")
      (node (ref "SV3") (pin "4") (pinfunction "4_4") (pintype "passive"))
    )
    (net (code "59") (name "unconnected-(SV3-Pad5)") (class "Default")
      (node (ref "SV3") (pin "5") (pinfunction "5_5") (pintype "passive"))
    )
    (net (code "60") (name "unconnected-(SV3-Pad6)") (class "Default")
      (node (ref "SV3") (pin "6") (pinfunction "6_6") (pintype "passive"))
    )
    (net (code "61") (name "unconnected-(SV3-Pad7)") (class "Default")
      (node (ref "SV3") (pin "7") (pinfunction "7_7") (pintype "passive"))
    )
    (net (code "62") (name "unconnected-(SV3-Pad8)") (class "Default")
      (node (ref "SV3") (pin "8") (pinfunction "8_8") (pintype "passive"))
    )
    (net (code "63") (name "unconnected-(SV3-Pad9)") (class "Default")
      (node (ref "SV3") (pin "9") (pinfunction "9_9") (pintype "passive"))
    )
    (net (code "64") (name "unconnected-(SV3-Pad10)") (class "Default")
      (node (ref "SV3") (pin "10") (pinfunction "10_10") (pintype "passive"))
    )
    (net (code "65") (name "unconnected-(SV3-Pad11)") (class "Default")
      (node (ref "SV3") (pin "11") (pinfunction "11_11") (pintype "passive"))
    )
    (net (code "66") (name "unconnected-(SV3-Pad13)") (class "Default")
      (node (ref "SV3") (pin "13") (pinfunction "13_13") (pintype "passive"))
    )
  )
)
